# FM_Transmitter_Eagle.net
KiCad netlist of a schematic drawn in EAGLE
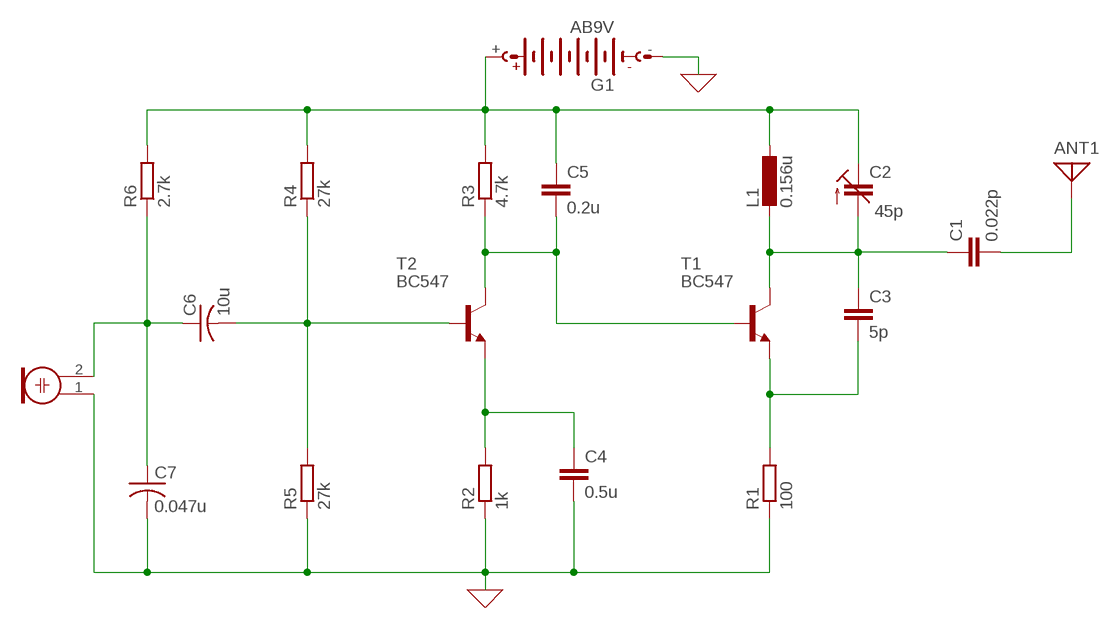
[diagram p0: schematic, sheet 1]

(export (version "E")
  (design (tool "Eeschema 10.0.6"))
  (components
    (comp (ref "ANT1")
      (value "ANTENNA")
      (footprint "eagle-import:PAD-01")
      (libsource (lib "eagle-import") (part "ANTENNA"))
    )
    (comp (ref "C1")
      (value "0.022p")
      (footprint "eagle-import:C025-024X044")
      (libsource (lib "eagle-import") (part "C-EU025-024X044"))
    )
    (comp (ref "C2")
      (value "45p")
      (footprint "eagle-import:CTRIM808-BC")
      (libsource (lib "eagle-import") (part "C-TRIMM808"))
    )
    (comp (ref "C3")
      (value "5p")
      (footprint "eagle-import:C025-024X044")
      (libsource (lib "eagle-import") (part "C-EU025-024X044"))
    )
    (comp (ref "C4")
      (value "0.5u")
      (footprint "eagle-import:C025-024X044")
      (libsource (lib "eagle-import") (part "C-EU025-024X044"))
    )
    (comp (ref "C5")
      (value "0.2u")
      (footprint "eagle-import:C025-024X044")
      (libsource (lib "eagle-import") (part "C-EU025-024X044"))
    )
    (comp (ref "C6")
      (value "10u")
      (footprint "eagle-import:C025-024X044")
      (libsource (lib "eagle-import") (part "C-US025-024X044"))
    )
    (comp (ref "C7")
      (value "0.047u")
      (footprint "eagle-import:C025-024X044")
      (libsource (lib "eagle-import") (part "C-US025-024X044"))
    )
    (comp (ref "G1")
      (value "AB9V")
      (footprint "eagle-import:AB9V")
      (libsource (lib "eagle-import") (part "AB9V"))
    )
    (comp (ref "L1")
      (value "0.156u")
      (footprint "eagle-import:0204_5")
      (libsource (lib "eagle-import") (part "L-EU0204/5"))
    )
    (comp (ref "M1")
      (value "ELECTRET_MICROPHON-F6050AP")
      (footprint "eagle-import:F6050AP")
      (libsource (lib "eagle-import") (part "ELECTRET_MICROPHON-F6050AP"))
    )
    (comp (ref "R1")
      (value "100")
      (footprint "eagle-import:0204_7")
      (libsource (lib "eagle-import") (part "R-EU_0204/7"))
    )
    (comp (ref "R2")
      (value "1k")
      (footprint "eagle-import:0204_7")
      (libsource (lib "eagle-import") (part "R-EU_0204/7"))
    )
    (comp (ref "R3")
      (value "4.7k")
      (footprint "eagle-import:0204_7")
      (libsource (lib "eagle-import") (part "R-EU_0204/7"))
    )
    (comp (ref "R4")
      (value "27k")
      (footprint "eagle-import:0204_7")
      (libsource (lib "eagle-import") (part "R-EU_0204/7"))
    )
    (comp (ref "R5")
      (value "27k")
      (footprint "eagle-import:0204_7")
      (libsource (lib "eagle-import") (part "R-EU_0204/7"))
    )
    (comp (ref "R6")
      (value "2.7k")
      (footprint "eagle-import:0204_7")
      (libsource (lib "eagle-import") (part "R-EU_0204/7"))
    )
    (comp (ref "T1")
      (value "BC547")
      (footprint "eagle-import:TO92")
      (libsource (lib "eagle-import") (part "BC547"))
    )
    (comp (ref "T2")
      (value "BC547")
      (footprint "eagle-import:TO92")
      (libsource (lib "eagle-import") (part "BC547"))
    )
  )
  (nets
    (net (code "1") (name "GND") (class "Default")
      (node (ref "C4") (pin "2") (pinfunction "2_2") (pintype "passive"))
      (node (ref "C7") (pin "2") (pinfunction "2_2") (pintype "passive"))
      (node (ref "G1") (pin "-") (pinfunction "-_-") (pintype "passive"))
      (node (ref "M1") (pin "1") (pinfunction "1_1") (pintype "passive"))
      (node (ref "R1") (pin "1") (pinfunction "1_1") (pintype "passive"))
      (node (ref "R2") (pin "1") (pinfunction "1_1") (pintype "passive"))
      (node (ref "R5") (pin "1") (pinfunction "1_1") (pintype "passive"))
    )
    (net (code "2") (name "Net-(ANT1-Pad1)") (class "Default")
      (node (ref "ANT1") (pin "1") (pinfunction "1_1") (pintype "output"))
      (node (ref "C1") (pin "2") (pinfunction "2_2") (pintype "passive"))
    )
    (net (code "3") (name "Net-(C2-A)") (class "Default")
      (node (ref "C1") (pin "1") (pinfunction "1_1") (pintype "passive"))
      (node (ref "C2") (pin "2") (pinfunction "A_2") (pintype "passive"))
      (node (ref "C3") (pin "1") (pinfunction "1_1") (pintype "passive"))
      (node (ref "L1") (pin "2") (pinfunction "2_2") (pintype "passive"))
      (node (ref "T1") (pin "3") (pinfunction "C_3") (pintype "passive"))
    )
    (net (code "4") (name "Net-(C2-E)") (class "Default")
      (node (ref "C2") (pin "1") (pinfunction "E_1") (pintype "passive"))
      (node (ref "C5") (pin "1") (pinfunction "1_1") (pintype "passive"))
      (node (ref "G1") (pin "+") (pinfunction "+_+") (pintype "passive"))
      (node (ref "L1") (pin "1") (pinfunction "1_1") (pintype "passive"))
      (node (ref "R3") (pin "2") (pinfunction "2_2") (pintype "passive"))
      (node (ref "R4") (pin "2") (pinfunction "2_2") (pintype "passive"))
      (node (ref "R6") (pin "2") (pinfunction "2_2") (pintype "passive"))
    )
    (net (code "5") (name "Net-(C6-Pad1)") (class "Default")
      (node (ref "C6") (pin "1") (pinfunction "1_1") (pintype "passive"))
      (node (ref "C7") (pin "1") (pinfunction "1_1") (pintype "passive"))
      (node (ref "M1") (pin "2") (pinfunction "2_2") (pintype "passive"))
      (node (ref "R6") (pin "1") (pinfunction "1_1") (pintype "passive"))
    )
    (net (code "6") (name "Net-(T1-B)") (class "Default")
      (node (ref "C5") (pin "2") (pinfunction "2_2") (pintype "passive"))
      (node (ref "R3") (pin "1") (pinfunction "1_1") (pintype "passive"))
      (node (ref "T1") (pin "2") (pinfunction "B_2") (pintype "passive"))
      (node (ref "T2") (pin "3") (pinfunction "C_3") (pintype "passive"))
    )
    (net (code "7") (name "Net-(T1-E)") (class "Default")
      (node (ref "C3") (pin "2") (pinfunction "2_2") (pintype "passive"))
      (node (ref "R1") (pin "2") (pinfunction "2_2") (pintype "passive"))
      (node (ref "T1") (pin "1") (pinfunction "E_1") (pintype "passive"))
    )
    (net (code "8") (name "Net-(T2-B)") (class "Default")
      (node (ref "C6") (pin "2") (pinfunction "2_2") (pintype "passive"))
      (node (ref "R4") (pin "1") (pinfunction "1_1") (pintype "passive"))
      (node (ref "R5") (pin "2") (pinfunction "2_2") (pintype "passive"))
      (node (ref "T2") (pin "2") (pinfunction "B_2") (pintype "passive"))
    )
    (net (code "9") (name "Net-(T2-E)") (class "Default")
      (node (ref "C4") (pin "1") (pinfunction "1_1") (pintype "passive"))
      (node (ref "R2") (pin "2") (pinfunction "2_2") (pintype "passive"))
      (node (ref "T2") (pin "1") (pinfunction "E_1") (pintype "passive"))
    )
  )
)
